# LiPOBattery.net
KiCad netlist of a schematic drawn in Altium Designer
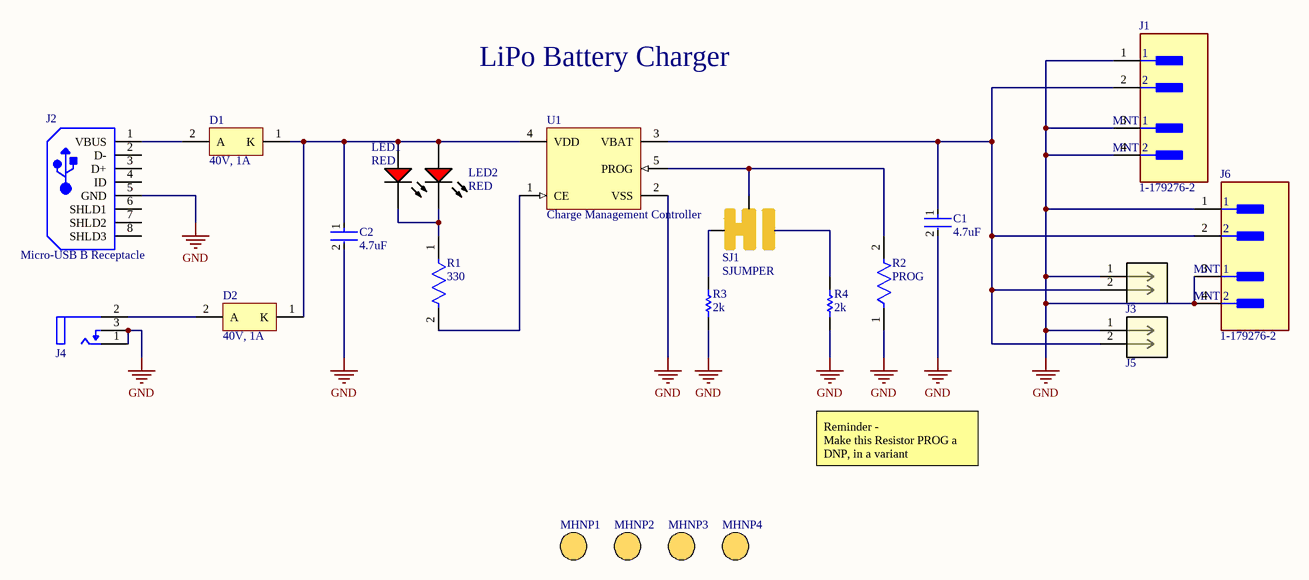
[diagram p0: LiPOBattery.SchDoc]

(export (version "E")
  (design (tool "Eeschema 10.0.6"))
  (components
    (comp (ref "C1")
      (value "4.7uF")
      (footprint "FP-CC0805-0_85-MFG")
      (description "CAP CER 4.7UF 6.3V X7R 0805")
      (fields (field (name "MANUFACTURER") "Yageo") (field (name "TOLERANCE") "0.1"))
      (libsource (lib "Altium Content Vault") (part "11868f565c42a9108669ba33697ecf6"))
    )
    (comp (ref "C2")
      (value "4.7uF")
      (footprint "FP-CC0805-0_85-MFG")
      (description "CAP CER 4.7UF 6.3V X7R 0805")
      (fields (field (name "MANUFACTURER") "Yageo") (field (name "TOLERANCE") "0.1"))
      (libsource (lib "Altium Content Vault") (part "11868f565c42a9108669ba33697ecf6"))
    )
    (comp (ref "D1")
      (value "40V, 1A")
      (footprint "ONSC-SMA-2-403D-02_V")
      (description "Schottky Power Rectifier, 2-Pin SMA, Pb-Free, Tape and Reel")
      (fields (field (name "PARTNUMBER") "MBRA140T3G") (field (name "MANUFACTURER") "On Semiconductor"))
      (libsource (lib "Altium Content Vault") (part "ONSC-D-K1A2-2_A"))
    )
    (comp (ref "D2")
      (value "40V, 1A")
      (footprint "ONSC-SMA-2-403D-02_V")
      (description "Schottky Power Rectifier, 2-Pin SMA, Pb-Free, Tape and Reel")
      (fields (field (name "PARTNUMBER") "MBRA140T3G") (field (name "MANUFACTURER") "On Semiconductor"))
      (libsource (lib "Altium Content Vault") (part "ONSC-D-K1A2-2_A"))
    )
    (comp (ref "J1")
      (value "1-179276-2")
      (footprint "FP-1-179276-2-MFG")
      (description "CONN HEADER R/A 2POS 5.08MM")
      (libsource (lib "Altium Content Vault") (part "56ec3178a87b3978bdc1b3682cd516a"))
    )
    (comp (ref "J2")
      (value "Micro-USB B Receptacle")
      (footprint "MOLX-105133-0001_V")
      (description "Micro-USB B Receptacle, Vertical, -30 to 85 degC, 5-Pin SMD, RoHS, Tape and Reel")
      (fields (field (name "MANUFACTURER") "Molex") (field (name "PARTNUMBER") "105133-0001"))
      (libsource (lib "Altium Content Vault") (part "USB-5-3SHLD"))
    )
    (comp (ref "J3")
      (value "2 POS VERT HEADER 0.001")
      (footprint "2Pins_AMP")
      (description "Description")
      (fields
        (field (name "MANUFACTURER_PART_NUMBER") "67997-402HLF")
        (field (name "COPYRIGHT") "Copyright (C) 2025 Ultra Librarian. All rights reserved.")
      )
      (libsource (lib "LiPOBattery") (part "67997-402HLF"))
    )
    (comp (ref "J4")
      (value "CONN PWR JACK 2.1X5.5MM SOLDER")
      (footprint "FP-RASM722PTR13X-MFG")
      (libsource (lib "Altium Content Vault") (part "69023cd999ddc70d2a190894d9bbb58"))
    )
    (comp (ref "J5")
      (value "2 POS VERT HEADER 0.001")
      (footprint "2Pins_AMP")
      (description "Description")
      (fields
        (field (name "MANUFACTURER_PART_NUMBER") "67997-402HLF")
        (field (name "COPYRIGHT") "Copyright (C) 2025 Ultra Librarian. All rights reserved.")
      )
      (libsource (lib "LiPOBattery") (part "67997-402HLF"))
    )
    (comp (ref "J6")
      (value "1-179276-2")
      (footprint "FP-1-179276-2-MFG")
      (description "CONN HEADER R/A 2POS 5.08MM")
      (libsource (lib "Altium Content Vault") (part "56ec3178a87b3978bdc1b3682cd516a"))
    )
    (comp (ref "LED1")
      (value "RED")
      (footprint "VISH-TLMS1000_V")
      (description "Low Current LED, 40 mW, 1.8 V, -40 to 100 degC, 2-Pin SMD (0603), RoHS, Tape and Reel")
      (fields (field (name "MANUFACTURER") "Vishay"))
      (libsource (lib "Altium Content Vault") (part "LED-RED-AK-2"))
    )
    (comp (ref "LED2")
      (value "RED")
      (footprint "VISH-TLMS1000_V")
      (description "Low Current LED, 40 mW, 1.8 V, -40 to 100 degC, 2-Pin SMD (0603), RoHS, Tape and Reel")
      (fields (field (name "MANUFACTURER") "Vishay"))
      (libsource (lib "Altium Content Vault") (part "LED-RED-AK-2"))
    )
    (comp (ref "MHNP1")
      (value "Mounting Hole Non Plated 3.2mm")
      (footprint "MTHNP3P2MM")
      (description "Mounting Hole Non Plated 3.2mm drill hole")
      (libsource (lib "LiPOBattery") (part "MTHNP3P2MM"))
    )
    (comp (ref "MHNP2")
      (value "Mounting Hole Non Plated 3.2mm")
      (footprint "MTHNP3P2MM")
      (description "Mounting Hole Non Plated 3.2mm drill hole")
      (libsource (lib "LiPOBattery") (part "MTHNP3P2MM"))
    )
    (comp (ref "MHNP3")
      (value "Mounting Hole Non Plated 3.2mm")
      (footprint "MTHNP3P2MM")
      (description "Mounting Hole Non Plated 3.2mm drill hole")
      (libsource (lib "LiPOBattery") (part "MTHNP3P2MM"))
    )
    (comp (ref "MHNP4")
      (value "Mounting Hole Non Plated 3.2mm")
      (footprint "MTHNP3P2MM")
      (description "Mounting Hole Non Plated 3.2mm drill hole")
      (libsource (lib "LiPOBattery") (part "MTHNP3P2MM"))
    )
    (comp (ref "R1")
      (value "330")
      (footprint "FP-CRCW0805-e3-MFG")
      (description "RES Thick Film, 330Ω, 1%, 0.125W, 100ppm/°C, 0805")
      (fields (field (name "TOLERANCE") "1%"))
      (libsource (lib "Altium Content Vault") (part "1029c3af85768c4190bb7ad29bc67b5"))
    )
    (comp (ref "R2")
      (value "PROG")
      (footprint "FP-RS02B-MFG")
      (description "Res Wirewound 12K Ohm 1% 3W ±20ppm/°C Ceramic Hi Temp Sil AXL Thru-Hole Bulk")
      (fields (field (name "TOLERANCE") "1%"))
      (libsource (lib "Altium Content Vault") (part "1029c3af85768c4190bb7ad29bc67b5"))
    )
    (comp (ref "R3")
      (value "2k")
      (footprint "RESC2013X70X40ML20T20")
      (fields (field (name "PART NUMBER") "ERJ-6GEYJ202V") (field (name "MANUFACTURER") "Panasonic"))
      (libsource (lib "Altium Content Vault") (part "RES"))
    )
    (comp (ref "R4")
      (value "2k")
      (footprint "RESC2013X70X40ML20T20")
      (fields (field (name "PART NUMBER") "ERJ-6GEYJ202V") (field (name "MANUFACTURER") "Panasonic"))
      (libsource (lib "Altium Content Vault") (part "RES"))
    )
    (comp (ref "SJ1")
      (value "SJUMPER")
      (footprint "SJUMPER-Footprint-1")
      (description "Solder jumper pad")
      (libsource (lib "Uddipa Dattudu Chavali") (part "SJUMPER-Symbol-1"))
    )
    (comp (ref "U1")
      (value "Charge Management Controller")
      (footprint "SOT-23-OT5_M")
      (libsource (lib "Altium Content Vault") (part "PM-BM-MCP7381X-SOT5"))
    )
  )
  (nets
    (net (code "1") (name "GND") (class "Default")
      (node (ref "C1") (pin "2") (pinfunction "2_2") (pintype "passive"))
      (node (ref "C2") (pin "2") (pinfunction "2_2") (pintype "passive"))
      (node (ref "J1") (pin "1") (pinfunction "1_1") (pintype "passive"))
      (node (ref "J1") (pin "3") (pinfunction "MNT_1_3") (pintype "passive"))
      (node (ref "J1") (pin "4") (pinfunction "MNT_2_4") (pintype "passive"))
      (node (ref "J2") (pin "5") (pinfunction "GND_5") (pintype "passive"))
      (node (ref "J3") (pin "1") (pinfunction "1_1") (pintype "passive"))
      (node (ref "J4") (pin "1") (pinfunction "TIP_TERMINAL(CENTER_PIN)_1") (pintype "passive"))
      (node (ref "J4") (pin "3") (pinfunction "SHUNT_TERMINAL_3") (pintype "passive"))
      (node (ref "J5") (pin "1") (pinfunction "1_1") (pintype "passive"))
      (node (ref "J6") (pin "1") (pinfunction "1_1") (pintype "passive"))
      (node (ref "J6") (pin "3") (pinfunction "MNT_1_3") (pintype "passive"))
      (node (ref "J6") (pin "4") (pinfunction "MNT_2_4") (pintype "passive"))
      (node (ref "R2") (pin "1") (pinfunction "1_1") (pintype "passive"))
      (node (ref "R3") (pin "1") (pinfunction "1_1") (pintype "passive"))
      (node (ref "R4") (pin "1") (pinfunction "1_1") (pintype "passive"))
      (node (ref "U1") (pin "2") (pinfunction "VSS_2") (pintype "power_in"))
    )
    (net (code "2") (name "Net-(D1-A)") (class "Default")
      (node (ref "D1") (pin "2") (pinfunction "A_2") (pintype "passive"))
      (node (ref "J2") (pin "1") (pinfunction "VBUS_1") (pintype "passive"))
    )
    (net (code "3") (name "Net-(D1-K)") (class "Default")
      (node (ref "C2") (pin "1") (pinfunction "1_1") (pintype "passive"))
      (node (ref "D1") (pin "1") (pinfunction "K_1") (pintype "passive"))
      (node (ref "D2") (pin "1") (pinfunction "K_1") (pintype "passive"))
      (node (ref "LED1") (pin "1") (pinfunction "A_1") (pintype "passive"))
      (node (ref "LED2") (pin "1") (pinfunction "A_1") (pintype "passive"))
      (node (ref "U1") (pin "4") (pinfunction "VDD_4") (pintype "power_in"))
    )
    (net (code "4") (name "Net-(D2-A)") (class "Default")
      (node (ref "D2") (pin "2") (pinfunction "A_2") (pintype "passive"))
      (node (ref "J4") (pin "2") (pinfunction "SLEEVE_TERMINAL_2") (pintype "passive"))
    )
    (net (code "5") (name "Net-(LED1-K)") (class "Default")
      (node (ref "LED1") (pin "2") (pinfunction "K_2") (pintype "passive"))
      (node (ref "LED2") (pin "2") (pinfunction "K_2") (pintype "passive"))
      (node (ref "R1") (pin "1") (pinfunction "1_1") (pintype "passive"))
    )
    (net (code "6") (name "Net-(R3-Pad2)") (class "Default")
      (node (ref "R3") (pin "2") (pinfunction "2_2") (pintype "passive"))
      (node (ref "SJ1") (pin "1") (pinfunction "1_1") (pintype "passive"))
    )
    (net (code "7") (name "Net-(R4-Pad2)") (class "Default")
      (node (ref "R4") (pin "2") (pinfunction "2_2") (pintype "passive"))
      (node (ref "SJ1") (pin "3") (pinfunction "3_3") (pintype "passive"))
    )
    (net (code "8") (name "Net-(U1-CE)") (class "Default")
      (node (ref "R1") (pin "2") (pinfunction "2_2") (pintype "passive"))
      (node (ref "U1") (pin "1") (pinfunction "CE_1") (pintype "input"))
    )
    (net (code "9") (name "Net-(U1-PROG)") (class "Default")
      (node (ref "R2") (pin "2") (pinfunction "2_2") (pintype "passive"))
      (node (ref "SJ1") (pin "2") (pinfunction "2_2") (pintype "passive"))
      (node (ref "U1") (pin "5") (pinfunction "PROG_5") (pintype "input"))
    )
    (net (code "10") (name "Net-(U1-VBAT)") (class "Default")
      (node (ref "C1") (pin "1") (pinfunction "1_1") (pintype "passive"))
      (node (ref "J1") (pin "2") (pinfunction "2_2") (pintype "passive"))
      (node (ref "J3") (pin "2") (pinfunction "2_2") (pintype "passive"))
      (node (ref "J5") (pin "2") (pinfunction "2_2") (pintype "passive"))
      (node (ref "J6") (pin "2") (pinfunction "2_2") (pintype "passive"))
      (node (ref "U1") (pin "3") (pinfunction "VBAT_3") (pintype "power_in"))
    )
    (net (code "11") (name "unconnected-(J2-D+-Pad3)") (class "Default")
      (node (ref "J2") (pin "3") (pinfunction "D+_3") (pintype "passive"))
    )
    (net (code "12") (name "unconnected-(J2-D--Pad2)") (class "Default")
      (node (ref "J2") (pin "2") (pinfunction "D-_2") (pintype "passive"))
    )
    (net (code "13") (name "unconnected-(J2-ID-Pad4)") (class "Default")
      (node (ref "J2") (pin "4") (pinfunction "ID_4") (pintype "passive"))
    )
    (net (code "14") (name "unconnected-(J2-SHLD1-Pad6)") (class "Default")
      (node (ref "J2") (pin "6") (pinfunction "SHLD1_6") (pintype "passive"))
    )
    (net (code "15") (name "unconnected-(J2-SHLD2-Pad7)") (class "Default")
      (node (ref "J2") (pin "7") (pinfunction "SHLD2_7") (pintype "passive"))
    )
    (net (code "16") (name "unconnected-(J2-SHLD3-Pad8)") (class "Default")
      (node (ref "J2") (pin "8") (pinfunction "SHLD3_8") (pintype "passive"))
    )
  )
)
